# adaptive.net
KiCad netlist of a schematic drawn in EAGLE
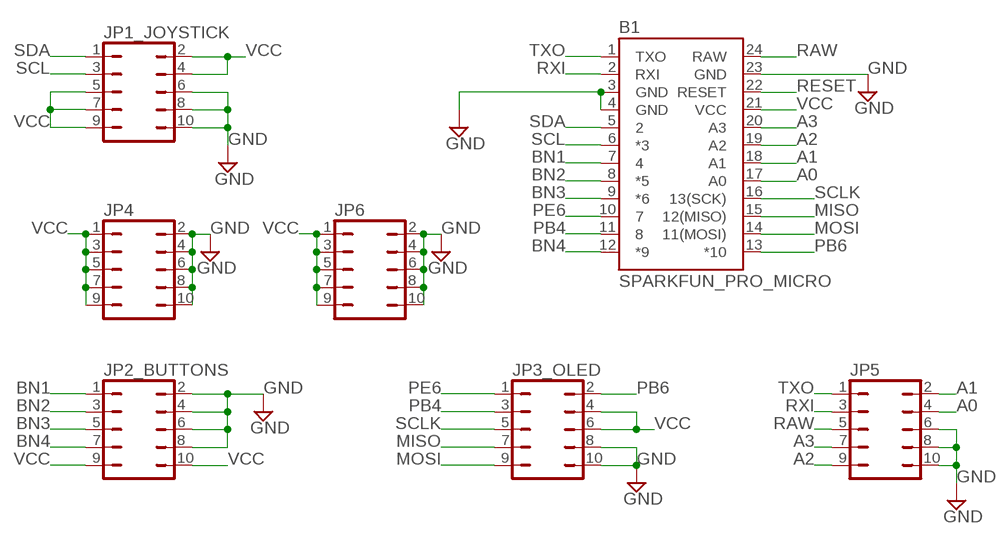
[diagram p0: schematic, sheet 1]

(export (version "E")
  (design (tool "Eeschema 10.0.6"))
  (components
    (comp (ref "B1")
      (value "SPARKFUN_PRO_MICRO")
      (footprint "eagle-import:SPARKFUN_PRO_MICRO")
      (libsource (lib "eagle-import") (part "SPARKFUN_PRO_MICRO"))
    )
    (comp (ref "JP1_JOYSTICK")
      (value "JP5Q")
      (footprint "eagle-import:JP5Q")
      (libsource (lib "eagle-import") (part "JP5Q"))
    )
    (comp (ref "JP2_BUTTONS")
      (value "JP5Q")
      (footprint "eagle-import:JP5Q")
      (libsource (lib "eagle-import") (part "JP5Q"))
    )
    (comp (ref "JP3_OLED")
      (value "JP5Q")
      (footprint "eagle-import:JP5Q")
      (libsource (lib "eagle-import") (part "JP5Q"))
    )
    (comp (ref "JP4")
      (value "JP5Q")
      (footprint "eagle-import:JP5Q")
      (libsource (lib "eagle-import") (part "JP5Q"))
    )
    (comp (ref "JP5")
      (value "JP5Q")
      (footprint "eagle-import:JP5Q")
      (libsource (lib "eagle-import") (part "JP5Q"))
    )
    (comp (ref "JP6")
      (value "JP5Q")
      (footprint "eagle-import:JP5Q")
      (libsource (lib "eagle-import") (part "JP5Q"))
    )
  )
  (nets
    (net (code "1") (name "A0") (class "Default")
      (node (ref "B1") (pin "17") (pinfunction "A0_17") (pintype "bidirectional"))
      (node (ref "JP5") (pin "4") (pinfunction "4_4") (pintype "passive"))
    )
    (net (code "2") (name "A1") (class "Default")
      (node (ref "B1") (pin "18") (pinfunction "A1_18") (pintype "bidirectional"))
      (node (ref "JP5") (pin "2") (pinfunction "2_2") (pintype "passive"))
    )
    (net (code "3") (name "A2") (class "Default")
      (node (ref "B1") (pin "19") (pinfunction "A2_19") (pintype "bidirectional"))
      (node (ref "JP5") (pin "9") (pinfunction "9_9") (pintype "passive"))
    )
    (net (code "4") (name "A3") (class "Default")
      (node (ref "B1") (pin "20") (pinfunction "A3_20") (pintype "bidirectional"))
      (node (ref "JP5") (pin "7") (pinfunction "7_7") (pintype "passive"))
    )
    (net (code "5") (name "BN1") (class "Default")
      (node (ref "B1") (pin "7") (pinfunction "4_7") (pintype "bidirectional"))
      (node (ref "JP2_BUTTONS") (pin "1") (pinfunction "1_1") (pintype "passive"))
    )
    (net (code "6") (name "BN2") (class "Default")
      (node (ref "B1") (pin "8") (pinfunction "*5_8") (pintype "bidirectional"))
      (node (ref "JP2_BUTTONS") (pin "3") (pinfunction "3_3") (pintype "passive"))
    )
    (net (code "7") (name "BN3") (class "Default")
      (node (ref "B1") (pin "9") (pinfunction "*6_9") (pintype "bidirectional"))
      (node (ref "JP2_BUTTONS") (pin "5") (pinfunction "5_5") (pintype "passive"))
    )
    (net (code "8") (name "BN4") (class "Default")
      (node (ref "B1") (pin "12") (pinfunction "*9_12") (pintype "bidirectional"))
      (node (ref "JP2_BUTTONS") (pin "7") (pinfunction "7_7") (pintype "passive"))
    )
    (net (code "9") (name "GND") (class "Default")
      (node (ref "B1") (pin "23") (pinfunction "GND_23") (pintype "power_in"))
      (node (ref "B1") (pin "3") (pinfunction "GND_3") (pintype "power_in"))
      (node (ref "B1") (pin "4") (pinfunction "GND_4") (pintype "power_in"))
      (node (ref "JP1_JOYSTICK") (pin "10") (pinfunction "10_10") (pintype "passive"))
      (node (ref "JP1_JOYSTICK") (pin "6") (pinfunction "6_6") (pintype "passive"))
      (node (ref "JP1_JOYSTICK") (pin "8") (pinfunction "8_8") (pintype "passive"))
      (node (ref "JP2_BUTTONS") (pin "2") (pinfunction "2_2") (pintype "passive"))
      (node (ref "JP2_BUTTONS") (pin "4") (pinfunction "4_4") (pintype "passive"))
      (node (ref "JP2_BUTTONS") (pin "6") (pinfunction "6_6") (pintype "passive"))
      (node (ref "JP2_BUTTONS") (pin "8") (pinfunction "8_8") (pintype "passive"))
      (node (ref "JP3_OLED") (pin "10") (pinfunction "10_10") (pintype "passive"))
      (node (ref "JP3_OLED") (pin "8") (pinfunction "8_8") (pintype "passive"))
      (node (ref "JP4") (pin "10") (pinfunction "10_10") (pintype "passive"))
      (node (ref "JP4") (pin "2") (pinfunction "2_2") (pintype "passive"))
      (node (ref "JP4") (pin "4") (pinfunction "4_4") (pintype "passive"))
      (node (ref "JP4") (pin "6") (pinfunction "6_6") (pintype "passive"))
      (node (ref "JP4") (pin "8") (pinfunction "8_8") (pintype "passive"))
      (node (ref "JP5") (pin "10") (pinfunction "10_10") (pintype "passive"))
      (node (ref "JP5") (pin "6") (pinfunction "6_6") (pintype "passive"))
      (node (ref "JP5") (pin "8") (pinfunction "8_8") (pintype "passive"))
      (node (ref "JP6") (pin "10") (pinfunction "10_10") (pintype "passive"))
      (node (ref "JP6") (pin "2") (pinfunction "2_2") (pintype "passive"))
      (node (ref "JP6") (pin "4") (pinfunction "4_4") (pintype "passive"))
      (node (ref "JP6") (pin "6") (pinfunction "6_6") (pintype "passive"))
      (node (ref "JP6") (pin "8") (pinfunction "8_8") (pintype "passive"))
    )
    (net (code "10") (name "MISO") (class "Default")
      (node (ref "B1") (pin "15") (pinfunction "12(MISO)_15") (pintype "bidirectional"))
      (node (ref "JP3_OLED") (pin "7") (pinfunction "7_7") (pintype "passive"))
    )
    (net (code "11") (name "MOSI") (class "Default")
      (node (ref "B1") (pin "14") (pinfunction "11(MOSI)_14") (pintype "bidirectional"))
      (node (ref "JP3_OLED") (pin "9") (pinfunction "9_9") (pintype "passive"))
    )
    (net (code "12") (name "PB4") (class "Default")
      (node (ref "B1") (pin "11") (pinfunction "8_11") (pintype "bidirectional"))
      (node (ref "JP3_OLED") (pin "3") (pinfunction "3_3") (pintype "passive"))
    )
    (net (code "13") (name "PB6") (class "Default")
      (node (ref "B1") (pin "13") (pinfunction "*10_13") (pintype "bidirectional"))
      (node (ref "JP3_OLED") (pin "2") (pinfunction "2_2") (pintype "passive"))
    )
    (net (code "14") (name "PE6") (class "Default")
      (node (ref "B1") (pin "10") (pinfunction "7_10") (pintype "bidirectional"))
      (node (ref "JP3_OLED") (pin "1") (pinfunction "1_1") (pintype "passive"))
    )
    (net (code "15") (name "RAW") (class "Default")
      (node (ref "B1") (pin "24") (pinfunction "RAW_24") (pintype "power_in"))
      (node (ref "JP5") (pin "5") (pinfunction "5_5") (pintype "passive"))
    )
    (net (code "16") (name "RESET") (class "Default")
      (node (ref "B1") (pin "22") (pinfunction "RESET_22") (pintype "bidirectional"))
    )
    (net (code "17") (name "RXI") (class "Default")
      (node (ref "B1") (pin "2") (pinfunction "RXI_2") (pintype "bidirectional"))
      (node (ref "JP5") (pin "3") (pinfunction "3_3") (pintype "passive"))
    )
    (net (code "18") (name "SCL") (class "Default")
      (node (ref "B1") (pin "6") (pinfunction "*3_6") (pintype "bidirectional"))
      (node (ref "JP1_JOYSTICK") (pin "3") (pinfunction "3_3") (pintype "passive"))
    )
    (net (code "19") (name "SCLK") (class "Default")
      (node (ref "B1") (pin "16") (pinfunction "13(SCK)_16") (pintype "bidirectional"))
      (node (ref "JP3_OLED") (pin "5") (pinfunction "5_5") (pintype "passive"))
    )
    (net (code "20") (name "SDA") (class "Default")
      (node (ref "B1") (pin "5") (pinfunction "2_5") (pintype "bidirectional"))
      (node (ref "JP1_JOYSTICK") (pin "1") (pinfunction "1_1") (pintype "passive"))
    )
    (net (code "21") (name "TXO") (class "Default")
      (node (ref "B1") (pin "1") (pinfunction "TXO_1") (pintype "bidirectional"))
      (node (ref "JP5") (pin "1") (pinfunction "1_1") (pintype "passive"))
    )
    (net (code "22") (name "VCC") (class "Default")
      (node (ref "B1") (pin "21") (pinfunction "VCC_21") (pintype "power_in"))
      (node (ref "JP1_JOYSTICK") (pin "2") (pinfunction "2_2") (pintype "passive"))
      (node (ref "JP1_JOYSTICK") (pin "4") (pinfunction "4_4") (pintype "passive"))
      (node (ref "JP1_JOYSTICK") (pin "5") (pinfunction "5_5") (pintype "passive"))
      (node (ref "JP1_JOYSTICK") (pin "7") (pinfunction "7_7") (pintype "passive"))
      (node (ref "JP1_JOYSTICK") (pin "9") (pinfunction "9_9") (pintype "passive"))
      (node (ref "JP2_BUTTONS") (pin "10") (pinfunction "10_10") (pintype "passive"))
      (node (ref "JP2_BUTTONS") (pin "9") (pinfunction "9_9") (pintype "passive"))
      (node (ref "JP3_OLED") (pin "4") (pinfunction "4_4") (pintype "passive"))
      (node (ref "JP3_OLED") (pin "6") (pinfunction "6_6") (pintype "passive"))
      (node (ref "JP4") (pin "1") (pinfunction "1_1") (pintype "passive"))
      (node (ref "JP4") (pin "3") (pinfunction "3_3") (pintype "passive"))
      (node (ref "JP4") (pin "5") (pinfunction "5_5") (pintype "passive"))
      (node (ref "JP4") (pin "7") (pinfunction "7_7") (pintype "passive"))
      (node (ref "JP4") (pin "9") (pinfunction "9_9") (pintype "passive"))
      (node (ref "JP6") (pin "1") (pinfunction "1_1") (pintype "passive"))
      (node (ref "JP6") (pin "3") (pinfunction "3_3") (pintype "passive"))
      (node (ref "JP6") (pin "5") (pinfunction "5_5") (pintype "passive"))
      (node (ref "JP6") (pin "7") (pinfunction "7_7") (pintype "passive"))
      (node (ref "JP6") (pin "9") (pinfunction "9_9") (pintype "passive"))
    )
  )
)
